# MiniVolter.net
KiCad netlist of a schematic drawn in EasyEDA Pro
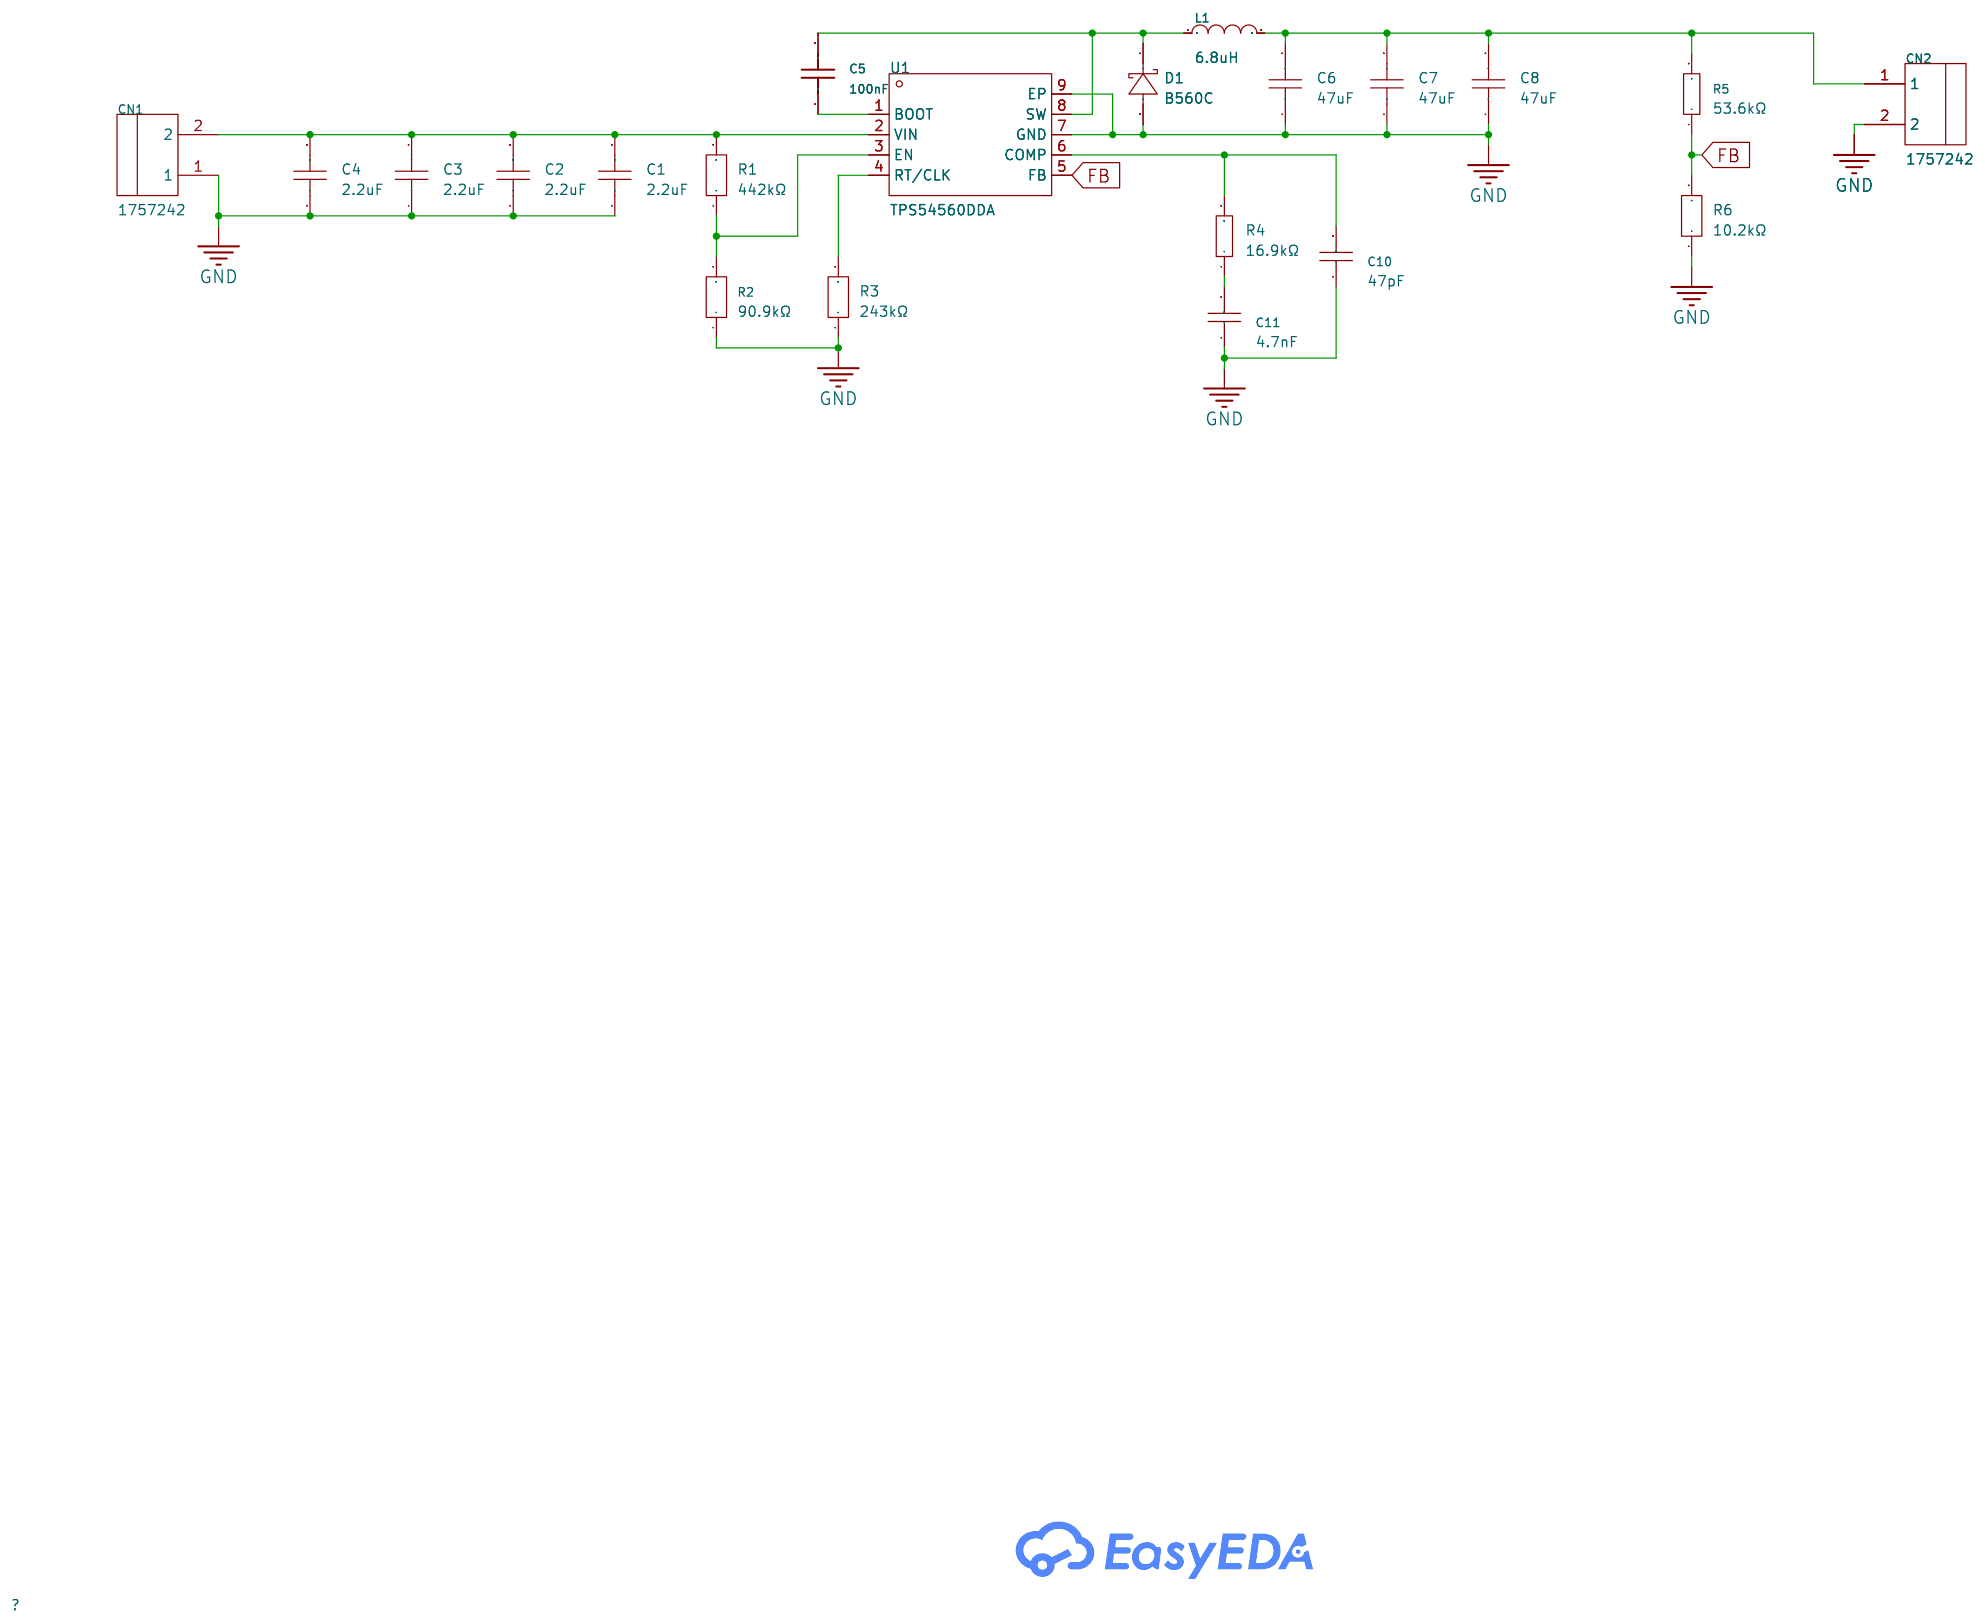
[diagram p0: schematic sheet]

(export (version "E")
  (design (tool "Eeschema 10.0.6"))
  (components
    (comp (ref "C1")
      (value "2.2uF")
      (footprint "easyedapro:C1206")
      (description "Capacitance:2.2uF Tolerance:±10% Tolerance:±10% Voltage Rating:100V Temperature Coefficient:X7R")
      (fields
        (field (name "Manufacturer Part") "CC1206KKX7R0BB225")
        (field (name "Manufacturer") "YAGEO(国巨)")
      )
      (libsource (lib "easyedapro") (part "CC1206KKX7R0BB225"))
    )
    (comp (ref "C2")
      (value "2.2uF")
      (footprint "easyedapro:C1206")
      (description "Capacitance:2.2uF Tolerance:±10% Tolerance:±10% Voltage Rating:100V Temperature Coefficient:X7R")
      (fields
        (field (name "Manufacturer Part") "CC1206KKX7R0BB225")
        (field (name "Manufacturer") "YAGEO(国巨)")
      )
      (libsource (lib "easyedapro") (part "CC1206KKX7R0BB225"))
    )
    (comp (ref "C3")
      (value "2.2uF")
      (footprint "easyedapro:C1206")
      (description "Capacitance:2.2uF Tolerance:±10% Tolerance:±10% Voltage Rating:100V Temperature Coefficient:X7R")
      (fields
        (field (name "Manufacturer Part") "CC1206KKX7R0BB225")
        (field (name "Manufacturer") "YAGEO(国巨)")
      )
      (libsource (lib "easyedapro") (part "CC1206KKX7R0BB225"))
    )
    (comp (ref "C4")
      (value "2.2uF")
      (footprint "easyedapro:C1206")
      (description "Capacitance:2.2uF Tolerance:±10% Tolerance:±10% Voltage Rating:100V Temperature Coefficient:X7R")
      (fields
        (field (name "Manufacturer Part") "CC1206KKX7R0BB225")
        (field (name "Manufacturer") "YAGEO(国巨)")
      )
      (libsource (lib "easyedapro") (part "CC1206KKX7R0BB225"))
    )
    (comp (ref "C5")
      (value "100nF")
      (footprint "easyedapro:C0603")
      (description "Capacitance:100nF Tolerance:±10% Tolerance:±10% Voltage Rating:50V Temperature Coefficient:X7R")
      (fields
        (field (name "Manufacturer Part") "CC0603KRX7R9BB104")
        (field (name "Manufacturer") "YAGEO(国巨)")
      )
      (libsource (lib "easyedapro") (part "CC0603KRX7R9BB104"))
    )
    (comp (ref "C6")
      (value "47uF")
      (footprint "easyedapro:C1210")
      (description "Capacitance:47uF Tolerance:±20% Tolerance:±20% Voltage Rating:25V Temperature Coefficient:X5R")
      (fields
        (field (name "Manufacturer Part") "HGC1210R5476M250NSVK")
        (field (name "Manufacturer") "Chinocera(华瓷)")
      )
      (libsource (lib "easyedapro") (part "HGC1210R5476M250NSVK"))
    )
    (comp (ref "C7")
      (value "47uF")
      (footprint "easyedapro:C1210")
      (description "Capacitance:47uF Tolerance:±20% Tolerance:±20% Voltage Rating:25V Temperature Coefficient:X5R")
      (fields
        (field (name "Manufacturer Part") "HGC1210R5476M250NSVK")
        (field (name "Manufacturer") "Chinocera(华瓷)")
      )
      (libsource (lib "easyedapro") (part "HGC1210R5476M250NSVK"))
    )
    (comp (ref "C8")
      (value "47uF")
      (footprint "easyedapro:C1210")
      (description "Capacitance:47uF Tolerance:±20% Tolerance:±20% Voltage Rating:25V Temperature Coefficient:X5R")
      (fields
        (field (name "Manufacturer Part") "HGC1210R5476M250NSVK")
        (field (name "Manufacturer") "Chinocera(华瓷)")
      )
      (libsource (lib "easyedapro") (part "HGC1210R5476M250NSVK"))
    )
    (comp (ref "C10")
      (value "47pF")
      (footprint "easyedapro:C0603")
      (description "Capacitance:47pF Tolerance:±5% Tolerance:±5% Voltage Rating:50V Temperature Coefficient:NP0")
      (fields
        (field (name "Manufacturer Part") "CC0603JRNPO9BN470")
        (field (name "Manufacturer") "YAGEO(国巨)")
      )
      (libsource (lib "easyedapro") (part "CC0603JRNPO9BN470"))
    )
    (comp (ref "C11")
      (value "4.7nF")
      (footprint "easyedapro:C0603")
      (description "Capacitance:4.7nF Tolerance:±10% Tolerance:±10% Voltage Rating:50V Temperature Coefficient:X7R")
      (fields
        (field (name "Manufacturer Part") "CL10B472KB8NNNC")
        (field (name "Manufacturer") "SAMSUNG(三星)")
      )
      (libsource (lib "easyedapro") (part "CL10B472KB8NNNC"))
    )
    (comp (ref "CN1")
      (value "1757242")
      (footprint "easyedapro:CONN-TH_2P-P5.08_1757242")
      (fields (field (name "Manufacturer") "Phoenix Contact(菲尼克斯)"))
      (libsource (lib "easyedapro") (part "1757242"))
    )
    (comp (ref "CN2")
      (value "1757242")
      (footprint "easyedapro:CONN-TH_2P-P5.08_1757242")
      (fields (field (name "Manufacturer") "Phoenix Contact(菲尼克斯)"))
      (libsource (lib "easyedapro") (part "1757242"))
    )
    (comp (ref "D1")
      (value "B560C")
      (footprint "easyedapro:SMC_L6.9-W5.9-LS7.9-RD")
      (fields (field (name "Manufacturer") "FUXINSEMI(富芯森美)"))
      (libsource (lib "easyedapro") (part "B560C_C6807784"))
    )
    (comp (ref "L1")
      (value "6.8uH")
      (footprint "easyedapro:IND-SMD_L6.5-W6.5_VISHAY")
      (fields
        (field (name "Manufacturer Part") "IHLP2525CZER6R8M01")
        (field (name "Manufacturer") "VISHAY(威世)")
      )
      (libsource (lib "easyedapro") (part "IHLP2525CZER6R8M01"))
    )
    (comp (ref "R1")
      (value "442kΩ")
      (footprint "easyedapro:R0805")
      (fields (field (name "Manufacturer Part") "FRC0805F4423TS") (field (name "Manufacturer") "FOJAN(富捷)"))
      (libsource (lib "easyedapro") (part "FRC0805F4423TS"))
    )
    (comp (ref "R2")
      (value "90.9kΩ")
      (footprint "easyedapro:R0603")
      (fields (field (name "Manufacturer Part") "ERJ3EKF9092V") (field (name "Manufacturer") "PANASONIC(松下)"))
      (libsource (lib "easyedapro") (part "ERJ3EKF9092V"))
    )
    (comp (ref "R3")
      (value "243kΩ")
      (footprint "easyedapro:R0603")
      (fields (field (name "Manufacturer Part") "FRC0603F2433TS") (field (name "Manufacturer") "FOJAN(富捷)"))
      (libsource (lib "easyedapro") (part "FRC0603F2433TS"))
    )
    (comp (ref "R4")
      (value "16.9kΩ")
      (footprint "easyedapro:R0603")
      (fields
        (field (name "Manufacturer Part") "0603WAF1692T5E")
        (field (name "Manufacturer") "UNI-ROYAL(厚声)")
      )
      (libsource (lib "easyedapro") (part "0603WAF1692T5E"))
    )
    (comp (ref "R5")
      (value "53.6kΩ")
      (footprint "easyedapro:R0603")
      (fields
        (field (name "Manufacturer Part") "0603WAF5362T5E")
        (field (name "Manufacturer") "UNI-ROYAL(厚声)")
      )
      (libsource (lib "easyedapro") (part "0603WAF5362T5E"))
    )
    (comp (ref "R6")
      (value "10.2kΩ")
      (footprint "easyedapro:R0603")
      (fields (field (name "Manufacturer Part") "FRC0603F1022TS") (field (name "Manufacturer") "FOJAN(富捷)"))
      (libsource (lib "easyedapro") (part "FRC0603F1022TS"))
    )
    (comp (ref "U1")
      (value "TPS54560DDA")
      (footprint "easyedapro:SO-8_L4.9-W3.9-P1.27-LS6.0-BL-EP")
      (fields (field (name "Manufacturer") "TI(德州仪器)"))
      (libsource (lib "easyedapro") (part "TPS54560DDA"))
    )
  )
  (nets
    (net (code "1") (name "FB") (class "Default")
      (node (ref "R5") (pin "1") (pinfunction "1_1") (pintype "input"))
      (node (ref "R6") (pin "2") (pinfunction "2_2") (pintype "unspecified"))
      (node (ref "U1") (pin "5") (pinfunction "FB_5") (pintype "unspecified"))
    )
    (net (code "2") (name "GND") (class "Default")
      (node (ref "C1") (pin "1") (pinfunction "1_1") (pintype "unspecified"))
      (node (ref "C10") (pin "1") (pinfunction "1_1") (pintype "input"))
      (node (ref "C11") (pin "1") (pinfunction "1_1") (pintype "input"))
      (node (ref "C2") (pin "1") (pinfunction "1_1") (pintype "unspecified"))
      (node (ref "C3") (pin "1") (pinfunction "1_1") (pintype "unspecified"))
      (node (ref "C4") (pin "1") (pinfunction "1_1") (pintype "unspecified"))
      (node (ref "C6") (pin "1") (pinfunction "1_1") (pintype "unspecified"))
      (node (ref "C7") (pin "1") (pinfunction "1_1") (pintype "unspecified"))
      (node (ref "C8") (pin "1") (pinfunction "1_1") (pintype "unspecified"))
      (node (ref "CN1") (pin "1") (pinfunction "1_1") (pintype "input"))
      (node (ref "CN2") (pin "2") (pinfunction "2_2") (pintype "input"))
      (node (ref "D1") (pin "2") (pinfunction "A_2") (pintype "unspecified"))
      (node (ref "R2") (pin "1") (pinfunction "1_1") (pintype "input"))
      (node (ref "R3") (pin "1") (pinfunction "1_1") (pintype "unspecified"))
      (node (ref "R6") (pin "1") (pinfunction "1_1") (pintype "unspecified"))
      (node (ref "U1") (pin "7") (pinfunction "GND_7") (pintype "unspecified"))
      (node (ref "U1") (pin "9") (pinfunction "EP_9") (pintype "unspecified"))
    )
    (net (code "3") (name "Net-(C6-Pad2)") (class "Default")
      (node (ref "C6") (pin "2") (pinfunction "2_2") (pintype "unspecified"))
      (node (ref "C7") (pin "2") (pinfunction "2_2") (pintype "unspecified"))
      (node (ref "C8") (pin "2") (pinfunction "2_2") (pintype "unspecified"))
      (node (ref "CN2") (pin "1") (pinfunction "1_1") (pintype "input"))
      (node (ref "L1") (pin "2") (pinfunction "2_2") (pintype "input"))
      (node (ref "R5") (pin "2") (pinfunction "2_2") (pintype "input"))
    )
    (net (code "4") (name "Net-(C11-Pad2)") (class "Default")
      (node (ref "C11") (pin "2") (pinfunction "2_2") (pintype "input"))
      (node (ref "R4") (pin "1") (pinfunction "1_1") (pintype "input"))
    )
    (net (code "5") (name "Net-(D1-K)") (class "Default")
      (node (ref "C5") (pin "2") (pinfunction "2_2") (pintype "unspecified"))
      (node (ref "D1") (pin "1") (pinfunction "K_1") (pintype "unspecified"))
      (node (ref "L1") (pin "1") (pinfunction "1_1") (pintype "input"))
      (node (ref "U1") (pin "8") (pinfunction "SW_8") (pintype "unspecified"))
    )
    (net (code "6") (name "Net-(U1-BOOT)") (class "Default")
      (node (ref "C5") (pin "1") (pinfunction "1_1") (pintype "unspecified"))
      (node (ref "U1") (pin "1") (pinfunction "BOOT_1") (pintype "unspecified"))
    )
    (net (code "7") (name "Net-(U1-COMP)") (class "Default")
      (node (ref "C10") (pin "2") (pinfunction "2_2") (pintype "input"))
      (node (ref "R4") (pin "2") (pinfunction "2_2") (pintype "input"))
      (node (ref "U1") (pin "6") (pinfunction "COMP_6") (pintype "unspecified"))
    )
    (net (code "8") (name "Net-(U1-EN)") (class "Default")
      (node (ref "R1") (pin "1") (pinfunction "1_1") (pintype "unspecified"))
      (node (ref "R2") (pin "2") (pinfunction "2_2") (pintype "input"))
      (node (ref "U1") (pin "3") (pinfunction "EN_3") (pintype "unspecified"))
    )
    (net (code "9") (name "Net-(U1-RT{slash}CLK)") (class "Default")
      (node (ref "R3") (pin "2") (pinfunction "2_2") (pintype "unspecified"))
      (node (ref "U1") (pin "4") (pinfunction "RT/CLK_4") (pintype "unspecified"))
    )
    (net (code "10") (name "Net-(U1-VIN)") (class "Default")
      (node (ref "C1") (pin "2") (pinfunction "2_2") (pintype "unspecified"))
      (node (ref "C2") (pin "2") (pinfunction "2_2") (pintype "unspecified"))
      (node (ref "C3") (pin "2") (pinfunction "2_2") (pintype "unspecified"))
      (node (ref "C4") (pin "2") (pinfunction "2_2") (pintype "unspecified"))
      (node (ref "CN1") (pin "2") (pinfunction "2_2") (pintype "input"))
      (node (ref "R1") (pin "2") (pinfunction "2_2") (pintype "unspecified"))
      (node (ref "U1") (pin "2") (pinfunction "VIN_2") (pintype "unspecified"))
    )
  )
)
